# 10_-MAIN_POWER.net
KiCad netlist of a schematic drawn in Altium Designer
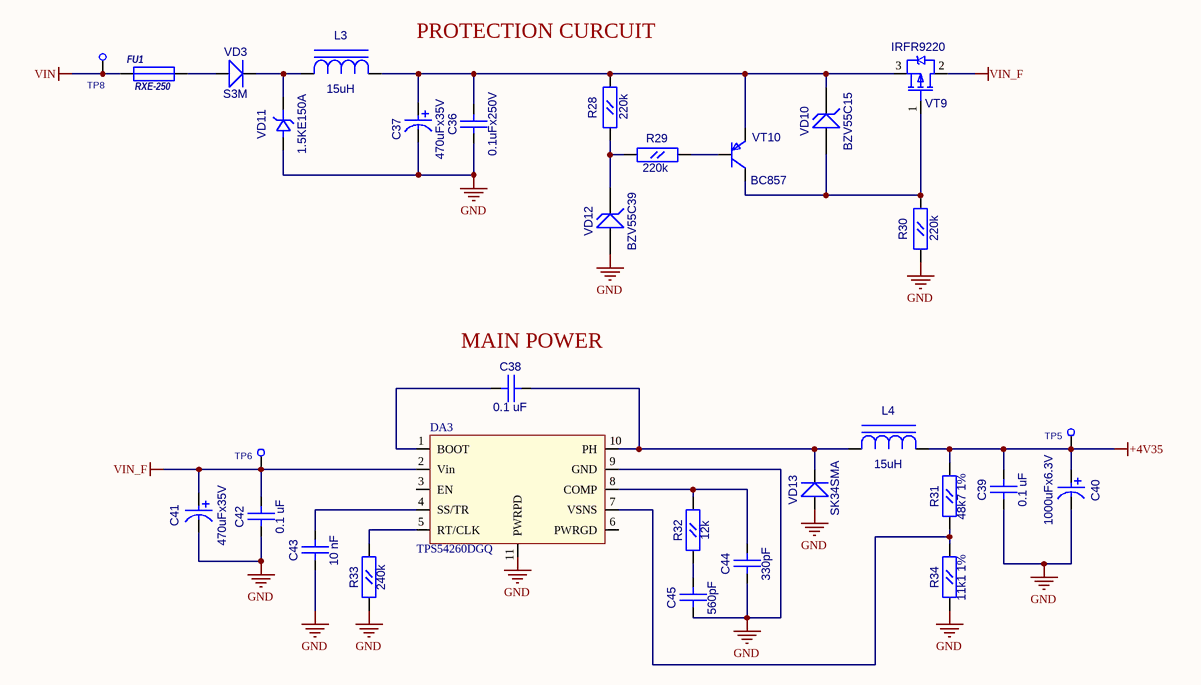
[diagram p0: [10]-MAIN_POWER.SchDoc]

(export (version "E")
  (design (tool "Eeschema 10.0.6"))
  (components
    (comp (ref "C36")
      (value "0.1uFx250V")
      (footprint "CC1206")
      (description "CC1206")
      (libsource (lib "gprs_modem_2") (part "CC1206"))
    )
    (comp (ref "C37")
      (value "470uFx35V")
      (footprint "CC16X10_CAP0.5(1)(Primary)")
      (description "CAP0.5(1)")
      (libsource (lib "gprs_modem_2") (part "CAP0.5(1)"))
    )
    (comp (ref "C38")
      (value "0.1 uF")
      (footprint "CC0603")
      (description "CC0603")
      (libsource (lib "gprs_modem_2") (part "CC0603"))
    )
    (comp (ref "C39")
      (value "0.1 uF")
      (footprint "CC0603")
      (description "CC0603")
      (libsource (lib "gprs_modem_2") (part "CC0603"))
    )
    (comp (ref "C40")
      (value "1000uFx6.3V")
      (footprint "CC8X3.5")
      (description "CAP0.35")
      (libsource (lib "gprs_modem_2") (part "CAP0.35"))
    )
    (comp (ref "C41")
      (value "470uFx35V")
      (footprint "CC16X10_CAP0.5(1)(Primary)")
      (description "CAP0.5(1)")
      (libsource (lib "gprs_modem_2") (part "CAP0.5(1)"))
    )
    (comp (ref "C42")
      (value "0.1 uF")
      (footprint "CC0603")
      (description "CC0603")
      (libsource (lib "gprs_modem_2") (part "CC0603"))
    )
    (comp (ref "C43")
      (value "10 nF")
      (footprint "CC0603")
      (description "CC0603")
      (libsource (lib "gprs_modem_2") (part "CC0603"))
    )
    (comp (ref "C44")
      (value "330pF")
      (footprint "CC0603")
      (description "CC0603")
      (libsource (lib "gprs_modem_2") (part "CC0603"))
    )
    (comp (ref "C45")
      (value "560pF")
      (footprint "CC0603")
      (description "CC0603")
      (libsource (lib "gprs_modem_2") (part "CC0603"))
    )
    (comp (ref "DA3")
      (value "TPS54260DGQ")
      (footprint "S-PDSO-G10")
      (libsource (lib "gprs_modem_2") (part "TPS54260DGQ"))
    )
    (comp (ref "FU1")
      (value "RXE-250")
      (footprint "RXE-185")
      (description "RXE-185")
      (libsource (lib "fizik_lib") (part "RXE-185"))
    )
    (comp (ref "L3")
      (value "15uH")
      (footprint "SDR0805")
      (description "SDR0805")
      (libsource (lib "gprs_modem_2") (part "SDR0805"))
    )
    (comp (ref "L4")
      (value "15uH")
      (footprint "SDR0805")
      (description "SDR0805")
      (libsource (lib "gprs_modem_2") (part "SDR0805"))
    )
    (comp (ref "R28")
      (value "220k")
      (footprint "RC0603")
      (description "RC0603")
      (libsource (lib "gprs_modem_2") (part "RC0603"))
    )
    (comp (ref "R29")
      (value "220k")
      (footprint "RC0603")
      (description "RC0603")
      (libsource (lib "gprs_modem_2") (part "RC0603"))
    )
    (comp (ref "R30")
      (value "220k")
      (footprint "RC0603")
      (description "RC0603")
      (libsource (lib "gprs_modem_2") (part "RC0603"))
    )
    (comp (ref "R31")
      (value "48k7 1%")
      (footprint "RC0603")
      (description "RC0603")
      (libsource (lib "gprs_modem_2") (part "RC0603"))
    )
    (comp (ref "R32")
      (value "12k")
      (footprint "RC0603")
      (description "RC0603")
      (libsource (lib "gprs_modem_2") (part "RC0603"))
    )
    (comp (ref "R33")
      (value "240k")
      (footprint "RC0603")
      (description "RC0603")
      (libsource (lib "gprs_modem_2") (part "RC0603"))
    )
    (comp (ref "R34")
      (value "11k1 1%")
      (footprint "RC0603")
      (description "RC0603")
      (libsource (lib "gprs_modem_2") (part "RC0603"))
    )
    (comp (ref "TP5")
      (value "TESTPOINT1")
      (footprint "TESTPOINT1")
      (libsource (lib "fizik_lib") (part "TESTPOINT1"))
    )
    (comp (ref "TP6")
      (value "TESTPOINT1")
      (footprint "TESTPOINT1")
      (libsource (lib "fizik_lib") (part "TESTPOINT1"))
    )
    (comp (ref "TP8")
      (value "TESTPOINT1")
      (footprint "TESTPOINT1")
      (libsource (lib "fizik_lib") (part "TESTPOINT1"))
    )
    (comp (ref "VD3")
      (value "S3M")
      (footprint "SMC")
      (description "Schottky Rectifier")
      (libsource (lib "fizik_lib") (part "S3A"))
    )
    (comp (ref "VD10")
      (value "BZV55C15")
      (footprint "SOD-80")
      (description "Zener Voltage Regulator Diode")
      (libsource (lib "gprs_modem_2") (part "BZV55C12"))
    )
    (comp (ref "VD11")
      (value "1.5KE150A")
      (footprint "DO-201")
      (description "1.5KE")
      (libsource (lib "gprs_modem") (part "1.5KE"))
    )
    (comp (ref "VD12")
      (value "BZV55C39")
      (footprint "SOD-80")
      (description "Zener Voltage Regulator Diode")
      (libsource (lib "gprs_modem_2") (part "BZV55C12"))
    )
    (comp (ref "VD13")
      (value "SK34SMA")
      (footprint "SMA")
      (description "Schottky Rectifier")
      (libsource (lib "gprs_modem") (part "SK34SMA"))
    )
    (comp (ref "VT9")
      (value "IRFR9220")
      (footprint "D-PAK(TO-252AA)")
      (description "HEXFET Power MOSFET")
      (libsource (lib "gprs_modem_2") (part "IRFR9220"))
    )
    (comp (ref "VT10")
      (value "BC857")
      (footprint "SOT-23(123)")
      (description "PNP 100ma transistor")
      (libsource (lib "gprs_modem_2") (part "BC857B"))
    )
  )
  (nets
    (net (code "1") (name "+4V35") (class "Default")
      (node (ref "C39") (pin "1") (pinfunction "A_1") (pintype "passive"))
      (node (ref "C40") (pin "1") (pintype "passive"))
      (node (ref "L4") (pin "2") (pinfunction "A_2") (pintype "passive"))
      (node (ref "R31") (pin "2") (pinfunction "B_2") (pintype "passive"))
      (node (ref "TP5") (pin "1") (pintype "passive"))
    )
    (net (code "2") (name "GND") (class "Default")
      (node (ref "C36") (pin "1") (pinfunction "A_1") (pintype "passive"))
      (node (ref "C37") (pin "1") (pintype "passive"))
      (node (ref "C39") (pin "2") (pinfunction "B_2") (pintype "passive"))
      (node (ref "C40") (pin "2") (pintype "passive"))
      (node (ref "C41") (pin "1") (pintype "passive"))
      (node (ref "C42") (pin "2") (pinfunction "B_2") (pintype "passive"))
      (node (ref "C43") (pin "2") (pinfunction "B_2") (pintype "passive"))
      (node (ref "C44") (pin "2") (pinfunction "B_2") (pintype "passive"))
      (node (ref "C45") (pin "2") (pinfunction "B_2") (pintype "passive"))
      (node (ref "DA3") (pin "11") (pinfunction "PWRPD_11") (pintype "passive"))
      (node (ref "DA3") (pin "9") (pinfunction "GND_9") (pintype "passive"))
      (node (ref "R30") (pin "1") (pinfunction "A_1") (pintype "passive"))
      (node (ref "R33") (pin "1") (pinfunction "A_1") (pintype "passive"))
      (node (ref "R34") (pin "1") (pinfunction "A_1") (pintype "passive"))
      (node (ref "VD11") (pin "1") (pinfunction "A_1") (pintype "passive"))
      (node (ref "VD12") (pin "1") (pinfunction "A_1") (pintype "passive"))
      (node (ref "VD13") (pin "1") (pinfunction "A_1") (pintype "passive"))
    )
    (net (code "3") (name "Net-(C36-B)") (class "Default")
      (node (ref "C36") (pin "2") (pinfunction "B_2") (pintype "passive"))
      (node (ref "C37") (pin "2") (pintype "passive"))
      (node (ref "L3") (pin "2") (pinfunction "A_2") (pintype "passive"))
      (node (ref "R28") (pin "2") (pinfunction "B_2") (pintype "passive"))
      (node (ref "VD10") (pin "2") (pintype "passive"))
      (node (ref "VT10") (pin "2") (pinfunction "E_2") (pintype "passive"))
      (node (ref "VT9") (pin "3") (pinfunction "S_3") (pintype "passive"))
    )
    (net (code "4") (name "Net-(C38-A)") (class "Default")
      (node (ref "C38") (pin "1") (pinfunction "A_1") (pintype "passive"))
      (node (ref "DA3") (pin "10") (pinfunction "PH_10") (pintype "passive"))
      (node (ref "L4") (pin "1") (pinfunction "C_1") (pintype "passive"))
      (node (ref "VD13") (pin "2") (pinfunction "K_2") (pintype "passive"))
    )
    (net (code "5") (name "Net-(C38-B)") (class "Default")
      (node (ref "C38") (pin "2") (pinfunction "B_2") (pintype "passive"))
      (node (ref "DA3") (pin "1") (pinfunction "BOOT_1") (pintype "passive"))
    )
    (net (code "6") (name "Net-(C43-A)") (class "Default")
      (node (ref "C43") (pin "1") (pinfunction "A_1") (pintype "passive"))
      (node (ref "DA3") (pin "4") (pinfunction "SS/TR_4") (pintype "passive"))
    )
    (net (code "7") (name "Net-(C44-A)") (class "Default")
      (node (ref "C44") (pin "1") (pinfunction "A_1") (pintype "passive"))
      (node (ref "DA3") (pin "8") (pinfunction "COMP_8") (pintype "passive"))
      (node (ref "R32") (pin "2") (pinfunction "B_2") (pintype "passive"))
    )
    (net (code "8") (name "Net-(C45-A)") (class "Default")
      (node (ref "C45") (pin "1") (pinfunction "A_1") (pintype "passive"))
      (node (ref "R32") (pin "1") (pinfunction "A_1") (pintype "passive"))
    )
    (net (code "9") (name "Net-(DA3-RT{slash}CLK)") (class "Default")
      (node (ref "DA3") (pin "5") (pinfunction "RT/CLK_5") (pintype "passive"))
      (node (ref "R33") (pin "2") (pinfunction "B_2") (pintype "passive"))
    )
    (net (code "10") (name "Net-(DA3-VSNS)") (class "Default")
      (node (ref "DA3") (pin "7") (pinfunction "VSNS_7") (pintype "passive"))
      (node (ref "R31") (pin "1") (pinfunction "A_1") (pintype "passive"))
      (node (ref "R34") (pin "2") (pinfunction "B_2") (pintype "passive"))
    )
    (net (code "11") (name "Net-(L3-C)") (class "Default")
      (node (ref "L3") (pin "1") (pinfunction "C_1") (pintype "passive"))
      (node (ref "VD11") (pin "2") (pinfunction "K_2") (pintype "passive"))
      (node (ref "VD3") (pin "2") (pinfunction "K_2") (pintype "passive"))
    )
    (net (code "12") (name "Net-(R28-A)") (class "Default")
      (node (ref "R28") (pin "1") (pinfunction "A_1") (pintype "passive"))
      (node (ref "R29") (pin "2") (pinfunction "B_2") (pintype "passive"))
      (node (ref "VD12") (pin "2") (pintype "passive"))
    )
    (net (code "13") (name "Net-(R29-A)") (class "Default")
      (node (ref "R29") (pin "1") (pinfunction "A_1") (pintype "passive"))
      (node (ref "VT10") (pin "1") (pinfunction "B_1") (pintype "passive"))
    )
    (net (code "14") (name "Net-(R30-B)") (class "Default")
      (node (ref "R30") (pin "2") (pinfunction "B_2") (pintype "passive"))
      (node (ref "VD10") (pin "1") (pinfunction "A_1") (pintype "passive"))
      (node (ref "VT10") (pin "3") (pinfunction "C_3") (pintype "passive"))
      (node (ref "VT9") (pin "1") (pinfunction "G_1") (pintype "passive"))
    )
    (net (code "15") (name "Net-(VD3-A)") (class "Default")
      (node (ref "FU1") (pin "2") (pintype "passive"))
      (node (ref "VD3") (pin "1") (pinfunction "A_1") (pintype "passive"))
    )
    (net (code "16") (name "VIN") (class "Default")
      (node (ref "FU1") (pin "1") (pintype "passive"))
      (node (ref "TP8") (pin "1") (pintype "passive"))
    )
    (net (code "17") (name "VIN_F") (class "Default")
      (node (ref "C41") (pin "2") (pintype "passive"))
      (node (ref "C42") (pin "1") (pinfunction "A_1") (pintype "passive"))
      (node (ref "DA3") (pin "2") (pinfunction "Vin_2") (pintype "passive"))
      (node (ref "TP6") (pin "1") (pintype "passive"))
      (node (ref "VT9") (pin "2") (pinfunction "D_2") (pintype "passive"))
    )
    (net (code "18") (name "unconnected-(DA3-EN-Pad3)") (class "Default")
      (node (ref "DA3") (pin "3") (pinfunction "EN_3") (pintype "passive"))
    )
    (net (code "19") (name "unconnected-(DA3-PWRGD-Pad6)") (class "Default")
      (node (ref "DA3") (pin "6") (pinfunction "PWRGD_6") (pintype "passive"))
    )
  )
)
